# seven_seg_thermocouple_one.net
KiCad netlist of a schematic drawn in EAGLE
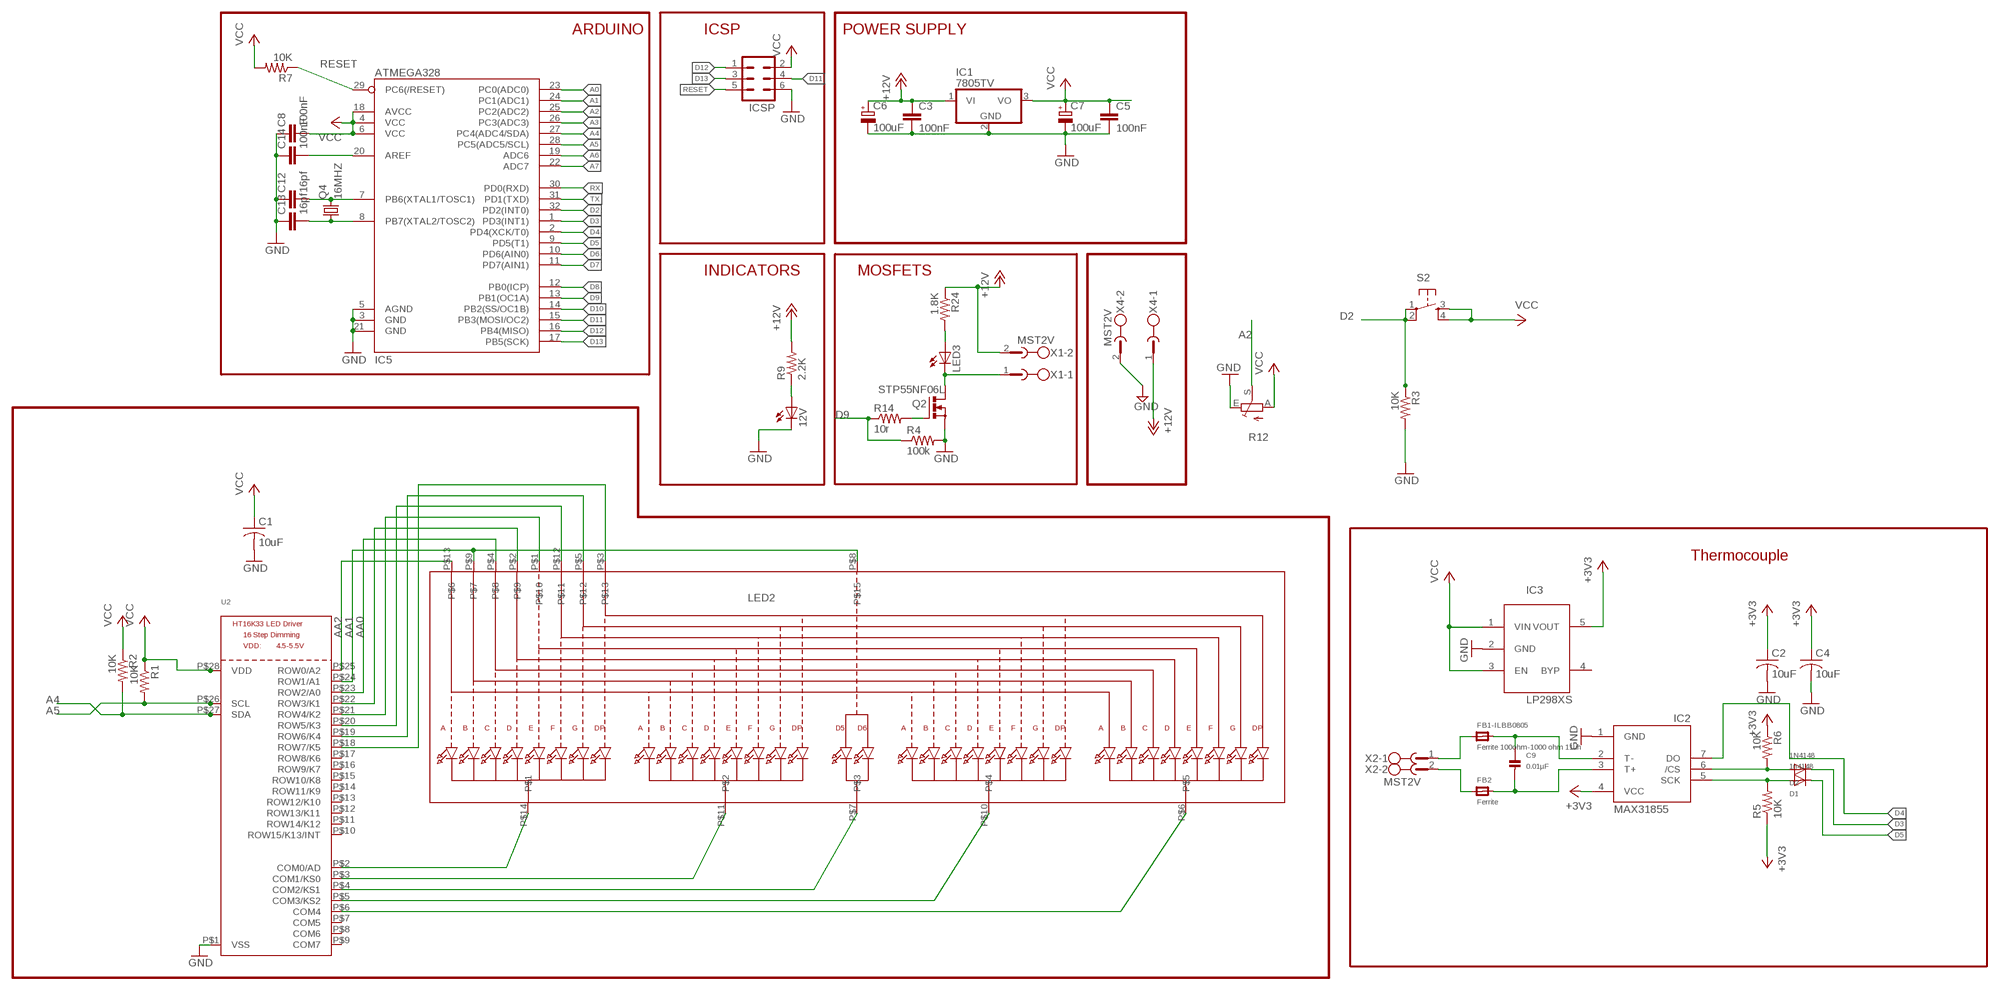
[diagram p0: schematic, sheet 1]

(export (version "E")
  (design (tool "Eeschema 10.0.6"))
  (components
    (comp (ref "12V")
      (value "LED0805")
      (footprint "eagle-import:LED-0805")
      (libsource (lib "eagle-import") (part "LED0805"))
    )
    (comp (ref "C1")
      (value "10uF")
      (footprint "eagle-import:C0805K")
      (libsource (lib "eagle-import") (part "C-USC0805K"))
    )
    (comp (ref "C2")
      (value "10uF")
      (footprint "eagle-import:C0805K")
      (libsource (lib "eagle-import") (part "C-USC0805K"))
    )
    (comp (ref "C3")
      (value "100nF")
      (footprint "eagle-import:0805")
      (libsource (lib "eagle-import") (part "CAP0805"))
    )
    (comp (ref "C4")
      (value "10uF")
      (footprint "eagle-import:C0805K")
      (libsource (lib "eagle-import") (part "C-USC0805K"))
    )
    (comp (ref "C5")
      (value "100nF")
      (footprint "eagle-import:0805")
      (libsource (lib "eagle-import") (part "CAP0805"))
    )
    (comp (ref "C6")
      (value "100uF")
      (footprint "eagle-import:E3,5-8")
      (libsource (lib "eagle-import") (part "CPOL-EUE3.5-8"))
    )
    (comp (ref "C7")
      (value "100uF")
      (footprint "eagle-import:E3,5-8")
      (libsource (lib "eagle-import") (part "CPOL-EUE3.5-8"))
    )
    (comp (ref "C8")
      (value "100nF")
      (footprint "eagle-import:0805")
      (libsource (lib "eagle-import") (part "CAP0805"))
    )
    (comp (ref "C9")
      (value "0.01µF")
      (footprint "eagle-import:_0805")
      (libsource (lib "eagle-import") (part "CAP_CERAMIC_0805"))
    )
    (comp (ref "C12")
      (value "16pf")
      (footprint "eagle-import:0805")
      (libsource (lib "eagle-import") (part "CAP0805"))
    )
    (comp (ref "C13")
      (value "16pf")
      (footprint "eagle-import:0805")
      (libsource (lib "eagle-import") (part "CAP0805"))
    )
    (comp (ref "C14")
      (value "100nF")
      (footprint "eagle-import:0805")
      (libsource (lib "eagle-import") (part "CAP0805"))
    )
    (comp (ref "D1")
      (value "1n4148")
      (footprint "eagle-import:SOD-323F")
      (libsource (lib "eagle-import") (part "DIODESOD-323F"))
    )
    (comp (ref "D2")
      (value "1N4148")
      (footprint "eagle-import:SOD-323F")
      (libsource (lib "eagle-import") (part "DIODESOD-323F"))
    )
    (comp (ref "FB1-ILBB0805")
      (value "Ferrite 100ohm-1000 ohm 11uh")
      (footprint "eagle-import:_0805")
      (libsource (lib "eagle-import") (part "FERRITE_0805"))
    )
    (comp (ref "FB2")
      (value "Ferrite")
      (footprint "eagle-import:_0805")
      (libsource (lib "eagle-import") (part "FERRITE_0805"))
    )
    (comp (ref "IC1")
      (value "7805TV")
      (footprint "eagle-import:TO220V")
      (libsource (lib "eagle-import") (part "78TV05"))
    )
    (comp (ref "IC2")
      (value "MAX31855")
      (footprint "eagle-import:SO08")
      (libsource (lib "eagle-import") (part "MAX6675"))
    )
    (comp (ref "IC3")
      (value "LP298XS")
      (footprint "eagle-import:SOT23-5L")
      (libsource (lib "eagle-import") (part "LP298XS"))
    )
    (comp (ref "IC5")
      (value "ATMEGA328")
      (footprint "eagle-import:TQFP32-08")
      (libsource (lib "eagle-import") (part "ATMEGA168"))
    )
    (comp (ref "ICSP")
      (value "ML6")
      (footprint "eagle-import:ML6")
      (libsource (lib "eagle-import") (part "ML6"))
    )
    (comp (ref "LED2")
      (value "DISP_SEGMENT_4DIGIT_BL-Q56C43")
      (footprint "eagle-import:SEGMENT-BL-Q56C43")
      (libsource (lib "eagle-import") (part "DISP_SEGMENT_4DIGIT_BL-Q56C43"))
    )
    (comp (ref "LED3")
      (value "LEDCHIP-LED0805")
      (footprint "eagle-import:CHIP-LED0805")
      (libsource (lib "eagle-import") (part "LEDCHIP-LED0805"))
    )
    (comp (ref "Q2")
      (value "STP55NF06L")
      (footprint "eagle-import:TO220BV")
      (libsource (lib "eagle-import") (part "IRF512"))
    )
    (comp (ref "Q4")
      (value "16MHZ")
      (footprint "eagle-import:HC49_S")
      (libsource (lib "eagle-import") (part "CRYSTALHC49S"))
    )
    (comp (ref "R1")
      (value "10K")
      (footprint "eagle-import:R0805")
      (libsource (lib "eagle-import") (part "R-US_R0805"))
    )
    (comp (ref "R2")
      (value "10K")
      (footprint "eagle-import:R0805")
      (libsource (lib "eagle-import") (part "R-US_R0805"))
    )
    (comp (ref "R3")
      (value "10K")
      (footprint "eagle-import:0805")
      (libsource (lib "eagle-import") (part "RESISTOR"))
    )
    (comp (ref "R4")
      (value "100k")
      (footprint "eagle-import:R0805")
      (libsource (lib "eagle-import") (part "R-US_R0805"))
    )
    (comp (ref "R5")
      (value "10K")
      (footprint "eagle-import:R0805")
      (libsource (lib "eagle-import") (part "R-US_R0805"))
    )
    (comp (ref "R6")
      (value "10K")
      (footprint "eagle-import:R0805")
      (libsource (lib "eagle-import") (part "R-US_R0805"))
    )
    (comp (ref "R7")
      (value "10K")
      (footprint "eagle-import:0805")
      (libsource (lib "eagle-import") (part "RESISTOR"))
    )
    (comp (ref "R9")
      (value "2.2K")
      (footprint "eagle-import:0805")
      (libsource (lib "eagle-import") (part "RESISTOR"))
    )
    (comp (ref "R12")
      (value "TRIM_EU-B25U")
      (footprint "eagle-import:B25U")
      (libsource (lib "eagle-import") (part "TRIM_EU-B25U"))
    )
    (comp (ref "R14")
      (value "10r")
      (footprint "eagle-import:M0805")
      (libsource (lib "eagle-import") (part "resistor_R-US_M0805"))
    )
    (comp (ref "R24")
      (value "1.8K")
      (footprint "eagle-import:R0805")
      (libsource (lib "eagle-import") (part "R-US_R0805"))
    )
    (comp (ref "S2")
      (value "TAC_SWITCHPTH")
      (footprint "eagle-import:TACTILE-PTH")
      (libsource (lib "eagle-import") (part "TAC_SWITCHPTH"))
    )
    (comp (ref "U2")
      (value "HT16K33_SOP28")
      (footprint "eagle-import:SOP28_300MIL")
      (libsource (lib "eagle-import") (part "HT16K33_SOP28"))
    )
    (comp (ref "X1")
      (value "MST2V")
      (footprint "eagle-import:MSTBV2")
      (libsource (lib "eagle-import") (part "MST2V"))
    )
    (comp (ref "X2")
      (value "MST2V")
      (footprint "eagle-import:MSTBV2")
      (libsource (lib "eagle-import") (part "MST2V"))
    )
    (comp (ref "X4")
      (value "MST2V")
      (footprint "eagle-import:MSTBV2")
      (libsource (lib "eagle-import") (part "MST2V"))
    )
  )
  (nets
    (net (code "1") (name "+3V3") (class "Default")
      (node (ref "C2") (pin "1") (pinfunction "1_1") (pintype "passive"))
      (node (ref "C4") (pin "1") (pinfunction "1_1") (pintype "passive"))
      (node (ref "IC2") (pin "4") (pinfunction "VCC_4") (pintype "power_in"))
      (node (ref "IC3") (pin "5") (pinfunction "VOUT_5") (pintype "bidirectional"))
      (node (ref "R5") (pin "1") (pinfunction "1_1") (pintype "passive"))
      (node (ref "R6") (pin "1") (pinfunction "1_1") (pintype "passive"))
    )
    (net (code "2") (name "+12V") (class "Default")
      (node (ref "C3") (pin "1") (pinfunction "1_1") (pintype "passive"))
      (node (ref "C6") (pin "+") (pinfunction "+_+") (pintype "passive"))
      (node (ref "IC1") (pin "1") (pinfunction "VI_1") (pintype "input"))
      (node (ref "R24") (pin "1") (pinfunction "1_1") (pintype "passive"))
      (node (ref "R9") (pin "2") (pinfunction "2_2") (pintype "passive"))
      (node (ref "X1") (pin "2") (pinfunction "1_2") (pintype "passive"))
      (node (ref "X4") (pin "1") (pinfunction "1_1") (pintype "passive"))
    )
    (net (code "3") (name "/AA0") (class "Default")
      (node (ref "LED2") (pin "P$4") (pinfunction "P$8_P$4") (pintype "bidirectional"))
      (node (ref "U2") (pin "P$23") (pinfunction "ROW2/A0_P$23") (pintype "bidirectional"))
    )
    (net (code "4") (name "/AA1") (class "Default")
      (node (ref "LED2") (pin "P$8") (pinfunction "P$15_P$8") (pintype "bidirectional"))
      (node (ref "LED2") (pin "P$9") (pinfunction "P$7_P$9") (pintype "bidirectional"))
      (node (ref "U2") (pin "P$24") (pinfunction "ROW1/A1_P$24") (pintype "bidirectional"))
    )
    (net (code "5") (name "/AA2") (class "Default")
      (node (ref "LED2") (pin "P$13") (pinfunction "P$6_P$13") (pintype "bidirectional"))
      (node (ref "U2") (pin "P$25") (pinfunction "ROW0/A2_P$25") (pintype "bidirectional"))
    )
    (net (code "6") (name "A0") (class "Default")
      (node (ref "IC5") (pin "23") (pinfunction "PC0(ADC0)_23") (pintype "bidirectional"))
    )
    (net (code "7") (name "A1") (class "Default")
      (node (ref "IC5") (pin "24") (pinfunction "PC1(ADC1)_24") (pintype "bidirectional"))
    )
    (net (code "8") (name "A2") (class "Default")
      (node (ref "IC5") (pin "25") (pinfunction "PC2(ADC2)_25") (pintype "bidirectional"))
      (node (ref "R12") (pin "S") (pinfunction "S_S") (pintype "passive"))
    )
    (net (code "9") (name "A3") (class "Default")
      (node (ref "IC5") (pin "26") (pinfunction "PC3(ADC3)_26") (pintype "bidirectional"))
    )
    (net (code "10") (name "A4") (class "Default")
      (node (ref "IC5") (pin "27") (pinfunction "PC4(ADC4/SDA)_27") (pintype "bidirectional"))
      (node (ref "R2") (pin "2") (pinfunction "2_2") (pintype "passive"))
      (node (ref "U2") (pin "P$27") (pinfunction "SDA_P$27") (pintype "bidirectional"))
    )
    (net (code "11") (name "A5") (class "Default")
      (node (ref "IC5") (pin "28") (pinfunction "PC5(ADC5/SCL)_28") (pintype "bidirectional"))
      (node (ref "R1") (pin "2") (pinfunction "2_2") (pintype "passive"))
      (node (ref "U2") (pin "P$26") (pinfunction "SCL_P$26") (pintype "bidirectional"))
    )
    (net (code "12") (name "A6") (class "Default")
      (node (ref "IC5") (pin "19") (pinfunction "ADC6_19") (pintype "bidirectional"))
    )
    (net (code "13") (name "A7") (class "Default")
      (node (ref "IC5") (pin "22") (pinfunction "ADC7_22") (pintype "bidirectional"))
    )
    (net (code "14") (name "D2") (class "Default")
      (node (ref "IC5") (pin "32") (pinfunction "PD2(INT0)_32") (pintype "bidirectional"))
      (node (ref "R3") (pin "1") (pinfunction "1_1") (pintype "passive"))
      (node (ref "S2") (pin "1") (pinfunction "1_1") (pintype "passive"))
      (node (ref "S2") (pin "2") (pinfunction "2_2") (pintype "passive"))
    )
    (net (code "15") (name "D3") (class "Default")
      (node (ref "D2") (pin "C") (pinfunction "C_C") (pintype "passive"))
      (node (ref "IC5") (pin "1") (pinfunction "PD3(INT1)_1") (pintype "bidirectional"))
    )
    (net (code "16") (name "D4") (class "Default")
      (node (ref "IC2") (pin "7") (pinfunction "DO_7") (pintype "output"))
      (node (ref "IC5") (pin "2") (pinfunction "PD4(XCK/T0)_2") (pintype "bidirectional"))
    )
    (net (code "17") (name "D5") (class "Default")
      (node (ref "D1") (pin "C") (pinfunction "C_C") (pintype "passive"))
      (node (ref "IC5") (pin "9") (pinfunction "PD5(T1)_9") (pintype "bidirectional"))
    )
    (net (code "18") (name "D6") (class "Default")
      (node (ref "IC5") (pin "10") (pinfunction "PD6(AIN0)_10") (pintype "bidirectional"))
    )
    (net (code "19") (name "D7") (class "Default")
      (node (ref "IC5") (pin "11") (pinfunction "PD7(AIN1)_11") (pintype "bidirectional"))
    )
    (net (code "20") (name "D8") (class "Default")
      (node (ref "IC5") (pin "12") (pinfunction "PB0(ICP)_12") (pintype "bidirectional"))
    )
    (net (code "21") (name "D9") (class "Default")
      (node (ref "IC5") (pin "13") (pinfunction "PB1(OC1A)_13") (pintype "bidirectional"))
      (node (ref "R14") (pin "1") (pinfunction "1_1") (pintype "passive"))
      (node (ref "R4") (pin "1") (pinfunction "1_1") (pintype "passive"))
    )
    (net (code "22") (name "D10") (class "Default")
      (node (ref "IC5") (pin "14") (pinfunction "PB2(SS/OC1B)_14") (pintype "bidirectional"))
    )
    (net (code "23") (name "D11") (class "Default")
      (node (ref "IC5") (pin "15") (pinfunction "PB3(MOSI/OC2)_15") (pintype "bidirectional"))
      (node (ref "ICSP") (pin "4") (pinfunction "4_4") (pintype "passive"))
    )
    (net (code "24") (name "D12") (class "Default")
      (node (ref "IC5") (pin "16") (pinfunction "PB4(MISO)_16") (pintype "bidirectional"))
      (node (ref "ICSP") (pin "1") (pinfunction "1_1") (pintype "passive"))
    )
    (net (code "25") (name "D13") (class "Default")
      (node (ref "IC5") (pin "17") (pinfunction "PB5(SCK)_17") (pintype "bidirectional"))
      (node (ref "ICSP") (pin "3") (pinfunction "3_3") (pintype "passive"))
    )
    (net (code "26") (name "GND") (class "Default")
      (node (ref "12V") (pin "C") (pinfunction "C_C") (pintype "passive"))
      (node (ref "C1") (pin "2") (pinfunction "2_2") (pintype "passive"))
      (node (ref "C12") (pin "1") (pinfunction "1_1") (pintype "passive"))
      (node (ref "C13") (pin "1") (pinfunction "1_1") (pintype "passive"))
      (node (ref "C14") (pin "1") (pinfunction "1_1") (pintype "passive"))
      (node (ref "C2") (pin "2") (pinfunction "2_2") (pintype "passive"))
      (node (ref "C3") (pin "2") (pinfunction "2_2") (pintype "passive"))
      (node (ref "C4") (pin "2") (pinfunction "2_2") (pintype "passive"))
      (node (ref "C5") (pin "2") (pinfunction "2_2") (pintype "passive"))
      (node (ref "C6") (pin "-") (pinfunction "-_-") (pintype "passive"))
      (node (ref "C7") (pin "-") (pinfunction "-_-") (pintype "passive"))
      (node (ref "C8") (pin "1") (pinfunction "1_1") (pintype "passive"))
      (node (ref "IC1") (pin "2") (pinfunction "GND_2") (pintype "passive"))
      (node (ref "IC2") (pin "1") (pinfunction "GND_1") (pintype "power_in"))
      (node (ref "IC3") (pin "2") (pinfunction "GND_2") (pintype "bidirectional"))
      (node (ref "IC5") (pin "21") (pinfunction "GND_21") (pintype "bidirectional"))
      (node (ref "IC5") (pin "3") (pinfunction "GND_3") (pintype "bidirectional"))
      (node (ref "IC5") (pin "5") (pinfunction "AGND_5") (pintype "bidirectional"))
      (node (ref "ICSP") (pin "6") (pinfunction "6_6") (pintype "passive"))
      (node (ref "Q2") (pin "S") (pinfunction "S_S") (pintype "passive"))
      (node (ref "R12") (pin "E") (pinfunction "E_E") (pintype "passive"))
      (node (ref "R3") (pin "2") (pinfunction "2_2") (pintype "passive"))
      (node (ref "R4") (pin "2") (pinfunction "2_2") (pintype "passive"))
      (node (ref "U2") (pin "P$1") (pinfunction "VSS_P$1") (pintype "bidirectional"))
      (node (ref "X4") (pin "2") (pinfunction "1_2") (pintype "passive"))
    )
    (net (code "27") (name "Net-(12V-PadA)") (class "Default")
      (node (ref "12V") (pin "A") (pinfunction "A_A") (pintype "passive"))
      (node (ref "R9") (pin "1") (pinfunction "1_1") (pintype "passive"))
    )
    (net (code "28") (name "Net-(C9-P$1)") (class "Default")
      (node (ref "C9") (pin "1") (pinfunction "P$1_1") (pintype "passive"))
      (node (ref "FB1-ILBB0805") (pin "2") (pinfunction "P$2_2") (pintype "passive"))
      (node (ref "IC2") (pin "2") (pinfunction "T-_2") (pintype "input"))
    )
    (net (code "29") (name "Net-(C9-P$2)") (class "Default")
      (node (ref "C9") (pin "2") (pinfunction "P$2_2") (pintype "passive"))
      (node (ref "FB2") (pin "2") (pinfunction "P$2_2") (pintype "passive"))
      (node (ref "IC2") (pin "3") (pinfunction "T+_3") (pintype "input"))
    )
    (net (code "30") (name "Net-(FB1-ILBB0805-P$1)") (class "Default")
      (node (ref "FB1-ILBB0805") (pin "1") (pinfunction "P$1_1") (pintype "passive"))
      (node (ref "X2") (pin "1") (pinfunction "1_1") (pintype "passive"))
    )
    (net (code "31") (name "Net-(FB2-P$1)") (class "Default")
      (node (ref "FB2") (pin "1") (pinfunction "P$1_1") (pintype "passive"))
      (node (ref "X2") (pin "2") (pinfunction "1_2") (pintype "passive"))
    )
    (net (code "32") (name "Net-(IC2-SCK)") (class "Default")
      (node (ref "D1") (pin "A") (pinfunction "A_A") (pintype "passive"))
      (node (ref "IC2") (pin "5") (pinfunction "SCK_5") (pintype "input"))
      (node (ref "R5") (pin "2") (pinfunction "2_2") (pintype "passive"))
    )
    (net (code "33") (name "Net-(IC2-{slash}CS)") (class "Default")
      (node (ref "D2") (pin "A") (pinfunction "A_A") (pintype "passive"))
      (node (ref "IC2") (pin "6") (pinfunction "/CS_6") (pintype "input"))
      (node (ref "R6") (pin "2") (pinfunction "2_2") (pintype "passive"))
    )
    (net (code "34") (name "Net-(IC5-AREF)") (class "Default")
      (node (ref "C14") (pin "2") (pinfunction "2_2") (pintype "passive"))
      (node (ref "IC5") (pin "20") (pinfunction "AREF_20") (pintype "bidirectional"))
    )
    (net (code "35") (name "Net-(IC5-PB6(XTAL1{slash}TOSC1))") (class "Default")
      (node (ref "C12") (pin "2") (pinfunction "2_2") (pintype "passive"))
      (node (ref "IC5") (pin "7") (pinfunction "PB6(XTAL1/TOSC1)_7") (pintype "bidirectional"))
      (node (ref "Q4") (pin "2") (pinfunction "2_2") (pintype "passive"))
    )
    (net (code "36") (name "Net-(IC5-PB7(XTAL2{slash}TOSC2))") (class "Default")
      (node (ref "C13") (pin "2") (pinfunction "2_2") (pintype "passive"))
      (node (ref "IC5") (pin "8") (pinfunction "PB7(XTAL2/TOSC2)_8") (pintype "bidirectional"))
      (node (ref "Q4") (pin "1") (pinfunction "1_1") (pintype "passive"))
    )
    (net (code "37") (name "Net-(LED2-P$1)") (class "Default")
      (node (ref "LED2") (pin "P$14") (pinfunction "P$1_P$14") (pintype "bidirectional"))
      (node (ref "U2") (pin "P$2") (pinfunction "COM0/AD_P$2") (pintype "bidirectional"))
    )
    (net (code "38") (name "Net-(LED2-P$2)") (class "Default")
      (node (ref "LED2") (pin "P$11") (pinfunction "P$2_P$11") (pintype "bidirectional"))
      (node (ref "U2") (pin "P$3") (pinfunction "COM1/KS0_P$3") (pintype "bidirectional"))
    )
    (net (code "39") (name "Net-(LED2-P$3)") (class "Default")
      (node (ref "LED2") (pin "P$7") (pinfunction "P$3_P$7") (pintype "bidirectional"))
      (node (ref "U2") (pin "P$4") (pinfunction "COM2/KS1_P$4") (pintype "bidirectional"))
    )
    (net (code "40") (name "Net-(LED2-P$4)") (class "Default")
      (node (ref "LED2") (pin "P$10") (pinfunction "P$4_P$10") (pintype "bidirectional"))
      (node (ref "U2") (pin "P$5") (pinfunction "COM3/KS2_P$5") (pintype "bidirectional"))
    )
    (net (code "41") (name "Net-(LED2-P$5)") (class "Default")
      (node (ref "LED2") (pin "P$6") (pinfunction "P$5_P$6") (pintype "bidirectional"))
      (node (ref "U2") (pin "P$6") (pinfunction "COM4_P$6") (pintype "bidirectional"))
    )
    (net (code "42") (name "Net-(LED2-P$9)") (class "Default")
      (node (ref "LED2") (pin "P$2") (pinfunction "P$9_P$2") (pintype "bidirectional"))
      (node (ref "U2") (pin "P$22") (pinfunction "ROW3/K1_P$22") (pintype "bidirectional"))
    )
    (net (code "43") (name "Net-(LED2-P$10)") (class "Default")
      (node (ref "LED2") (pin "P$1") (pinfunction "P$10_P$1") (pintype "bidirectional"))
      (node (ref "U2") (pin "P$21") (pinfunction "ROW4/K2_P$21") (pintype "bidirectional"))
    )
    (net (code "44") (name "Net-(LED2-P$11)") (class "Default")
      (node (ref "LED2") (pin "P$12") (pinfunction "P$11_P$12") (pintype "bidirectional"))
      (node (ref "U2") (pin "P$20") (pinfunction "ROW5/K3_P$20") (pintype "bidirectional"))
    )
    (net (code "45") (name "Net-(LED2-P$12)") (class "Default")
      (node (ref "LED2") (pin "P$5") (pinfunction "P$12_P$5") (pintype "bidirectional"))
      (node (ref "U2") (pin "P$19") (pinfunction "ROW6/K4_P$19") (pintype "bidirectional"))
    )
    (net (code "46") (name "Net-(LED2-P$13)") (class "Default")
      (node (ref "LED2") (pin "P$3") (pinfunction "P$13_P$3") (pintype "bidirectional"))
      (node (ref "U2") (pin "P$18") (pinfunction "ROW7/K5_P$18") (pintype "bidirectional"))
    )
    (net (code "47") (name "Net-(LED3-PadA)") (class "Default")
      (node (ref "LED3") (pin "A") (pinfunction "A_A") (pintype "passive"))
      (node (ref "R24") (pin "2") (pinfunction "2_2") (pintype "passive"))
    )
    (net (code "48") (name "Net-(LED3-PadC)") (class "Default")
      (node (ref "LED3") (pin "C") (pinfunction "C_C") (pintype "passive"))
      (node (ref "Q2") (pin "D") (pinfunction "D_D") (pintype "passive"))
      (node (ref "X1") (pin "1") (pinfunction "1_1") (pintype "passive"))
    )
    (net (code "49") (name "Net-(Q2-PadG)") (class "Default")
      (node (ref "Q2") (pin "G") (pinfunction "G_G") (pintype "passive"))
      (node (ref "R14") (pin "2") (pinfunction "2_2") (pintype "passive"))
    )
    (net (code "50") (name "RESET") (class "Default")
      (node (ref "IC5") (pin "29") (pinfunction "PC6(/RESET)_29") (pintype "bidirectional"))
      (node (ref "ICSP") (pin "5") (pinfunction "5_5") (pintype "passive"))
      (node (ref "R7") (pin "1") (pinfunction "1_1") (pintype "passive"))
    )
    (net (code "51") (name "RX") (class "Default")
      (node (ref "IC5") (pin "30") (pinfunction "PD0(RXD)_30") (pintype "bidirectional"))
    )
    (net (code "52") (name "TX") (class "Default")
      (node (ref "IC5") (pin "31") (pinfunction "PD1(TXD)_31") (pintype "bidirectional"))
    )
    (net (code "53") (name "VCC") (class "Default")
      (node (ref "C1") (pin "1") (pinfunction "1_1") (pintype "passive"))
      (node (ref "C5") (pin "1") (pinfunction "1_1") (pintype "passive"))
      (node (ref "C7") (pin "+") (pinfunction "+_+") (pintype "passive"))
      (node (ref "C8") (pin "2") (pinfunction "2_2") (pintype "passive"))
      (node (ref "IC1") (pin "3") (pinfunction "VO_3") (pintype "passive"))
      (node (ref "IC3") (pin "1") (pinfunction "VIN_1") (pintype "bidirectional"))
      (node (ref "IC3") (pin "3") (pinfunction "EN_3") (pintype "bidirectional"))
      (node (ref "IC5") (pin "18") (pinfunction "AVCC_18") (pintype "bidirectional"))
      (node (ref "IC5") (pin "4") (pinfunction "VCC_4") (pintype "bidirectional"))
      (node (ref "IC5") (pin "6") (pinfunction "VCC_6") (pintype "bidirectional"))
      (node (ref "ICSP") (pin "2") (pinfunction "2_2") (pintype "passive"))
      (node (ref "R1") (pin "1") (pinfunction "1_1") (pintype "passive"))
      (node (ref "R12") (pin "A") (pinfunction "A_A") (pintype "passive"))
      (node (ref "R2") (pin "1") (pinfunction "1_1") (pintype "passive"))
      (node (ref "R7") (pin "2") (pinfunction "2_2") (pintype "passive"))
      (node (ref "S2") (pin "3") (pinfunction "3_3") (pintype "passive"))
      (node (ref "S2") (pin "4") (pinfunction "4_4") (pintype "passive"))
      (node (ref "U2") (pin "P$28") (pinfunction "VDD_P$28") (pintype "bidirectional"))
    )
    (net (code "54") (name "unconnected-(IC3-BYP-Pad4)") (class "Default")
      (node (ref "IC3") (pin "4") (pinfunction "BYP_4") (pintype "bidirectional"))
    )
    (net (code "55") (name "unconnected-(U2-COM5-PadP$7)") (class "Default")
      (node (ref "U2") (pin "P$7") (pinfunction "COM5_P$7") (pintype "bidirectional"))
    )
    (net (code "56") (name "unconnected-(U2-COM6-PadP$8)") (class "Default")
      (node (ref "U2") (pin "P$8") (pinfunction "COM6_P$8") (pintype "bidirectional"))
    )
    (net (code "57") (name "unconnected-(U2-COM7-PadP$9)") (class "Default")
      (node (ref "U2") (pin "P$9") (pinfunction "COM7_P$9") (pintype "bidirectional"))
    )
    (net (code "58") (name "unconnected-(U2-ROW8{slash}K6-PadP$17)") (class "Default")
      (node (ref "U2") (pin "P$17") (pinfunction "ROW8/K6_P$17") (pintype "bidirectional"))
    )
    (net (code "59") (name "unconnected-(U2-ROW9{slash}K7-PadP$16)") (class "Default")
      (node (ref "U2") (pin "P$16") (pinfunction "ROW9/K7_P$16") (pintype "bidirectional"))
    )
    (net (code "60") (name "unconnected-(U2-ROW10{slash}K8-PadP$15)") (class "Default")
      (node (ref "U2") (pin "P$15") (pinfunction "ROW10/K8_P$15") (pintype "bidirectional"))
    )
    (net (code "61") (name "unconnected-(U2-ROW11{slash}K9-PadP$14)") (class "Default")
      (node (ref "U2") (pin "P$14") (pinfunction "ROW11/K9_P$14") (pintype "bidirectional"))
    )
    (net (code "62") (name "unconnected-(U2-ROW12{slash}K10-PadP$13)") (class "Default")
      (node (ref "U2") (pin "P$13") (pinfunction "ROW12/K10_P$13") (pintype "bidirectional"))
    )
    (net (code "63") (name "unconnected-(U2-ROW13{slash}K11-PadP$12)") (class "Default")
      (node (ref "U2") (pin "P$12") (pinfunction "ROW13/K11_P$12") (pintype "bidirectional"))
    )
    (net (code "64") (name "unconnected-(U2-ROW14{slash}K12-PadP$11)") (class "Default")
      (node (ref "U2") (pin "P$11") (pinfunction "ROW14/K12_P$11") (pintype "bidirectional"))
    )
    (net (code "65") (name "unconnected-(U2-ROW15{slash}K13{slash}INT-PadP$10)") (class "Default")
      (node (ref "U2") (pin "P$10") (pinfunction "ROW15/K13/INT_P$10") (pintype "bidirectional"))
    )
  )
)
